# Super_Hub.net
KiCad netlist of a schematic drawn in EasyEDA Pro
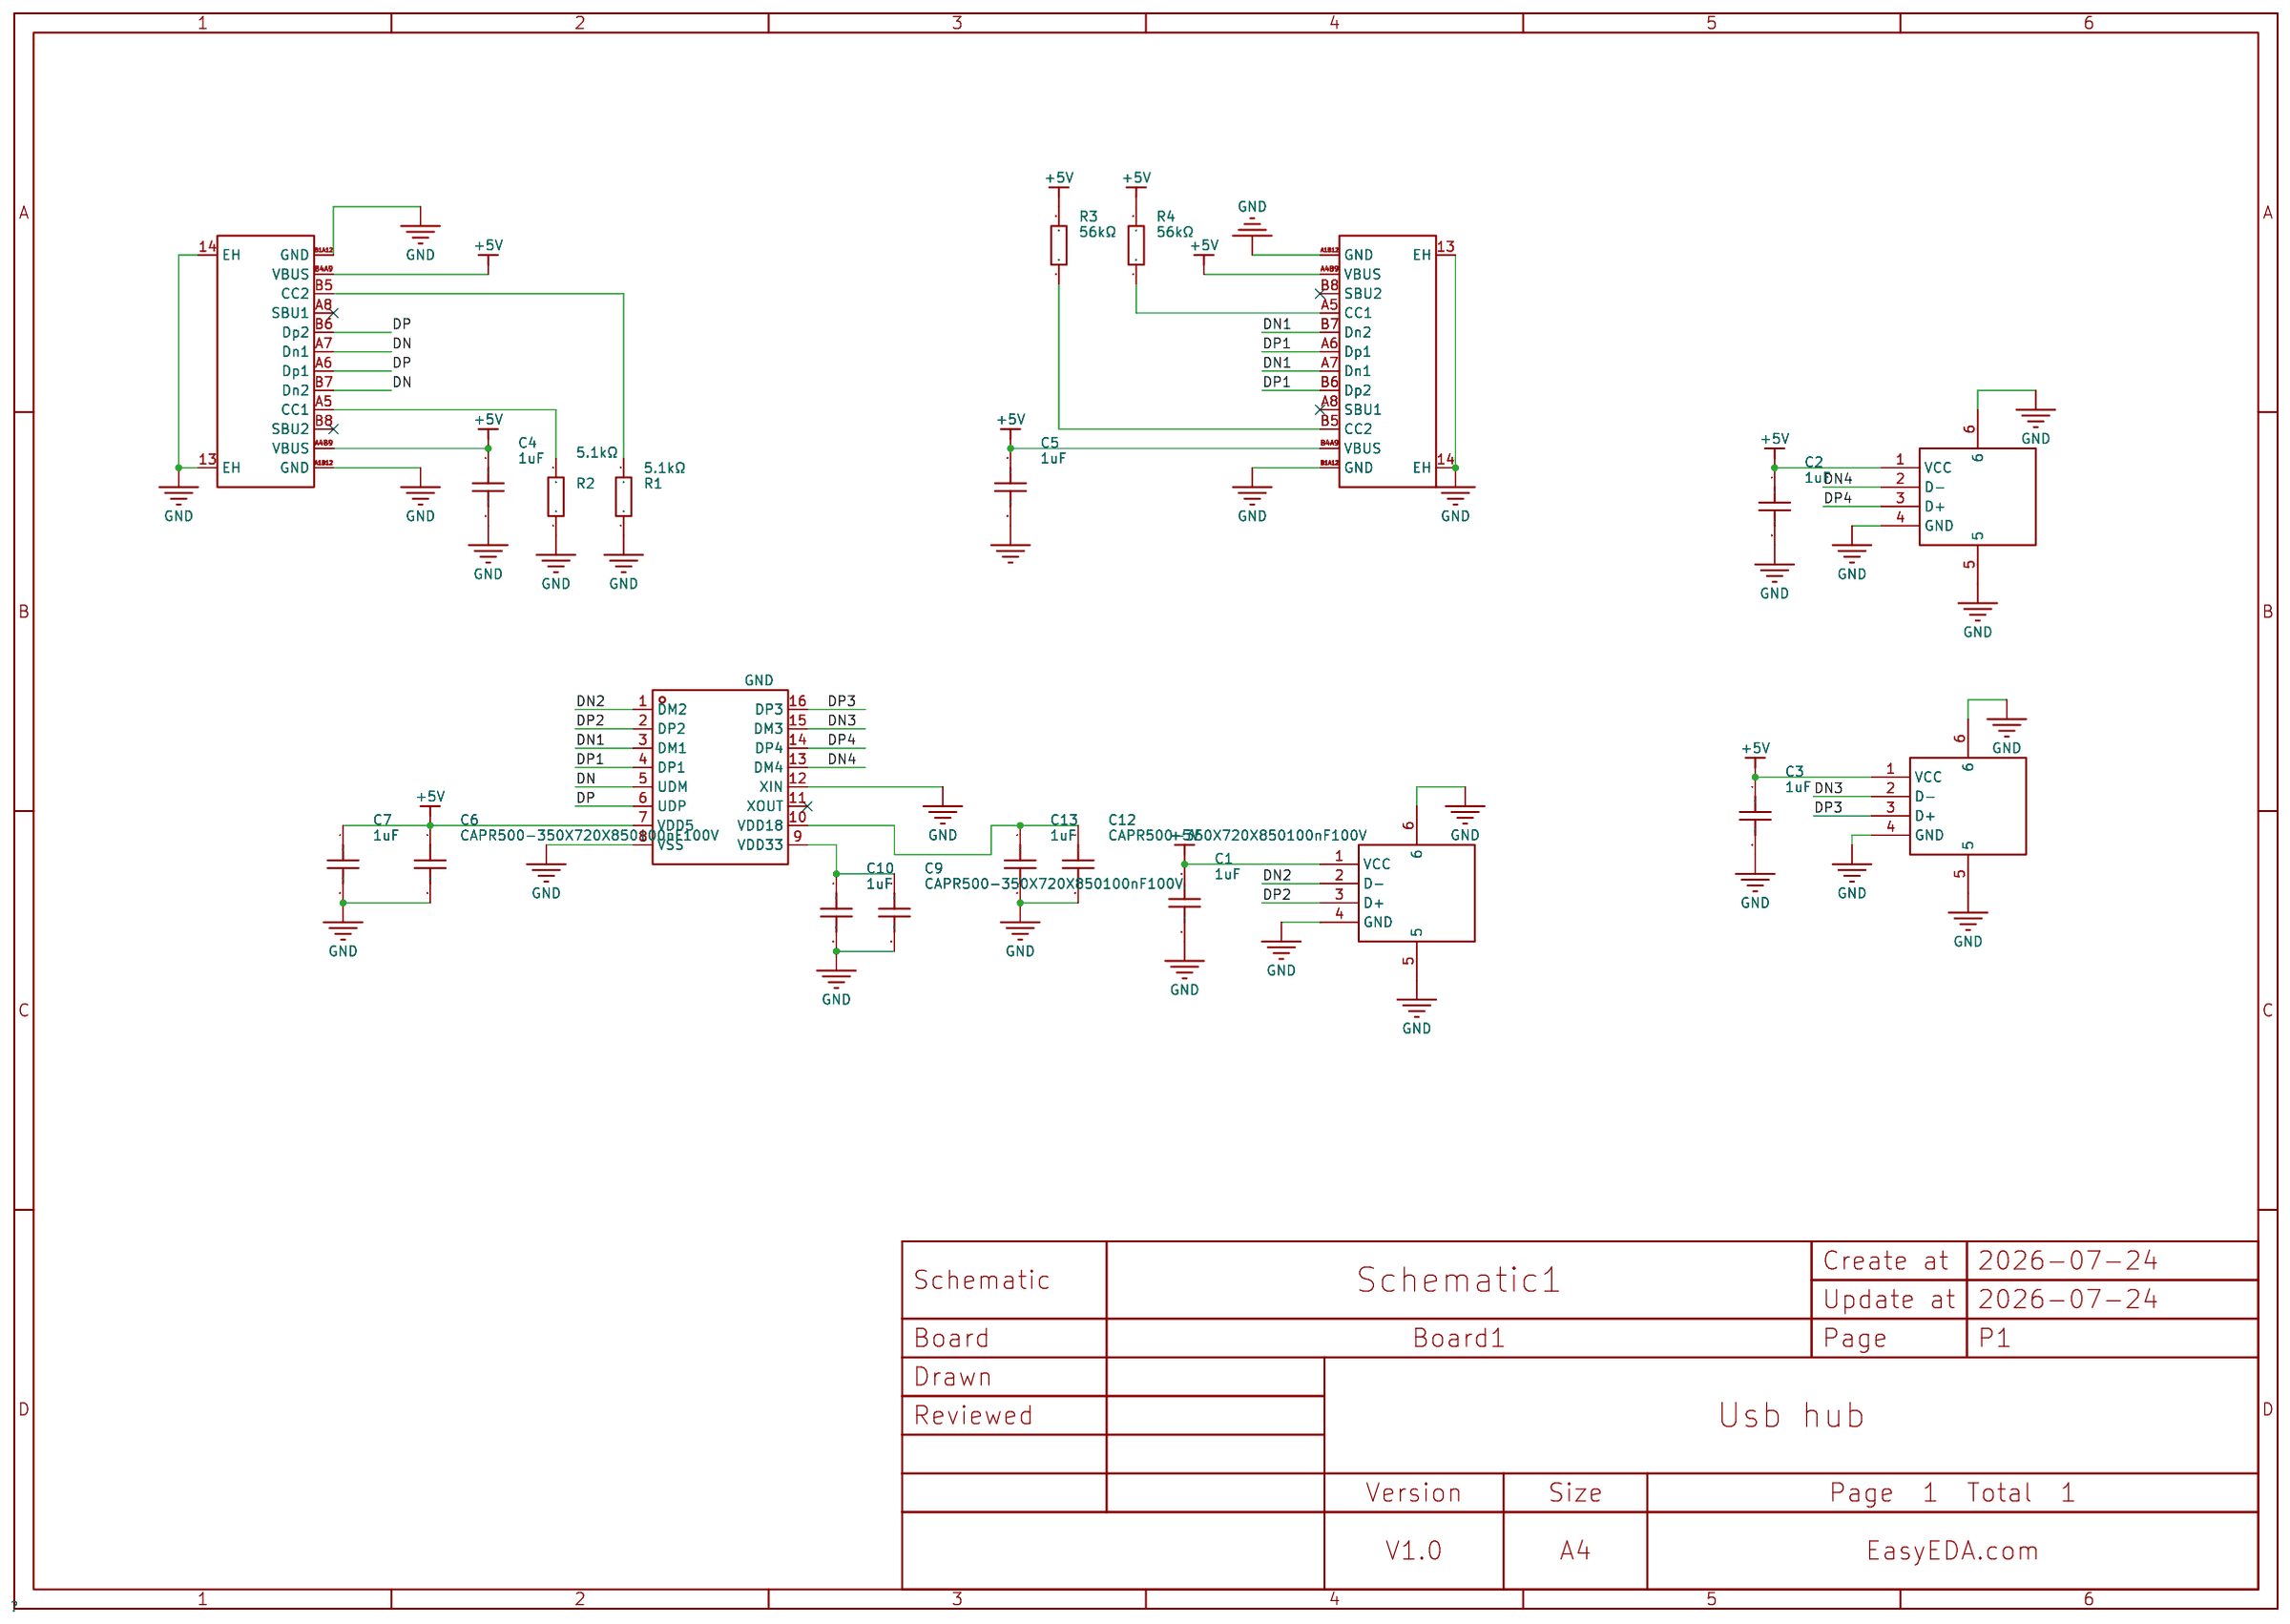
[diagram p0: schematic sheet]

(export (version "E")
  (design (tool "Eeschema 10.0.6"))
  (components
    (comp (ref "C1")
      (value "1uF")
      (footprint "easyedapro:C0603")
      (description "Capacitance:1uF Tolerance:±10% Tolerance:±10% Voltage Rating:50V Temperature Coefficient:X5R")
      (fields
        (field (name "Manufacturer Part") "CL10A105KB8NNNC")
        (field (name "Manufacturer") "SAMSUNG(三星)")
      )
      (libsource (lib "easyedapro") (part "CAP_OLD"))
    )
    (comp (ref "C2")
      (value "1uF")
      (footprint "easyedapro:C0603")
      (description "Capacitance:1uF Tolerance:±10% Tolerance:±10% Voltage Rating:50V Temperature Coefficient:X5R")
      (fields
        (field (name "Manufacturer Part") "CL10A105KB8NNNC")
        (field (name "Manufacturer") "SAMSUNG(三星)")
      )
      (libsource (lib "easyedapro") (part "CAP_OLD"))
    )
    (comp (ref "C3")
      (value "1uF")
      (footprint "easyedapro:C0603")
      (description "Capacitance:1uF Tolerance:±10% Tolerance:±10% Voltage Rating:50V Temperature Coefficient:X5R")
      (fields
        (field (name "Manufacturer Part") "CL10A105KB8NNNC")
        (field (name "Manufacturer") "SAMSUNG(三星)")
      )
      (libsource (lib "easyedapro") (part "CAP_OLD"))
    )
    (comp (ref "C4")
      (value "1uF")
      (footprint "easyedapro:C0603")
      (description "Capacitance:1uF Tolerance:±10% Tolerance:±10% Voltage Rating:50V Temperature Coefficient:X5R")
      (fields
        (field (name "Manufacturer Part") "CL10A105KB8NNNC")
        (field (name "Manufacturer") "SAMSUNG(三星)")
      )
      (libsource (lib "easyedapro") (part "CAP_OLD"))
    )
    (comp (ref "C5")
      (value "1uF")
      (footprint "easyedapro:C0603")
      (description "Capacitance:1uF Tolerance:±10% Tolerance:±10% Voltage Rating:50V Temperature Coefficient:X5R")
      (fields
        (field (name "Manufacturer Part") "CL10A105KB8NNNC")
        (field (name "Manufacturer") "SAMSUNG(三星)")
      )
      (libsource (lib "easyedapro") (part "CAP_OLD"))
    )
    (comp (ref "C6")
      (value "CAPR500-350X720X850100nF100V")
      (footprint "easyedapro:C0603")
      (libsource (lib "easyedapro") (part "CAP_OLD"))
    )
    (comp (ref "C7")
      (value "1uF")
      (footprint "easyedapro:C0603")
      (description "Capacitance:1uF Tolerance:±10% Tolerance:±10% Voltage Rating:50V Temperature Coefficient:X5R")
      (fields
        (field (name "Manufacturer Part") "CL10A105KB8NNNC")
        (field (name "Manufacturer") "SAMSUNG(三星)")
      )
      (libsource (lib "easyedapro") (part "CAP_OLD"))
    )
    (comp (ref "C9")
      (value "CAPR500-350X720X850100nF100V")
      (footprint "easyedapro:C0603")
      (libsource (lib "easyedapro") (part "CAP_OLD"))
    )
    (comp (ref "C10")
      (value "1uF")
      (footprint "easyedapro:C0603")
      (description "Capacitance:1uF Tolerance:±10% Tolerance:±10% Voltage Rating:50V Temperature Coefficient:X5R")
      (fields
        (field (name "Manufacturer Part") "CL10A105KB8NNNC")
        (field (name "Manufacturer") "SAMSUNG(三星)")
      )
      (libsource (lib "easyedapro") (part "CAP_OLD"))
    )
    (comp (ref "C12")
      (value "CAPR500-350X720X850100nF100V")
      (footprint "easyedapro:C0603")
      (libsource (lib "easyedapro") (part "CAP_OLD"))
    )
    (comp (ref "C13")
      (value "1uF")
      (footprint "easyedapro:C0603")
      (description "Capacitance:1uF Tolerance:±10% Tolerance:±10% Voltage Rating:50V Temperature Coefficient:X5R")
      (fields
        (field (name "Manufacturer Part") "CL10A105KB8NNNC")
        (field (name "Manufacturer") "SAMSUNG(三星)")
      )
      (libsource (lib "easyedapro") (part "CAP_OLD"))
    )
    (comp (ref "R1")
      (value "5.1kΩ")
      (footprint "easyedapro:R0603")
      (fields
        (field (name "Manufacturer Part") "0603WAF5101T5E")
        (field (name "Manufacturer") "UNI-ROYAL(厚声)")
        (field (name "Tolerance") "±1%")
      )
      (libsource (lib "easyedapro") (part "Res"))
    )
    (comp (ref "R2")
      (value "5.1kΩ")
      (footprint "easyedapro:R0603")
      (fields
        (field (name "Manufacturer Part") "0603WAF5101T5E")
        (field (name "Manufacturer") "UNI-ROYAL(厚声)")
        (field (name "Tolerance") "±1%")
      )
      (libsource (lib "easyedapro") (part "Res"))
    )
    (comp (ref "R3")
      (value "56kΩ")
      (footprint "easyedapro:R0603")
      (fields
        (field (name "Manufacturer Part") "0603WAF5602T5E")
        (field (name "Manufacturer") "UNI-ROYAL(厚声)")
        (field (name "Tolerance") "±1%")
      )
      (libsource (lib "easyedapro") (part "Res"))
    )
    (comp (ref "R4")
      (value "56kΩ")
      (footprint "easyedapro:R0603")
      (fields
        (field (name "Manufacturer Part") "0603WAF5602T5E")
        (field (name "Manufacturer") "UNI-ROYAL(厚声)")
        (field (name "Tolerance") "±1%")
      )
      (libsource (lib "easyedapro") (part "Res"))
    )
    (comp (ref "U1")
      (value "SL2.1s")
      (footprint "easyedapro:SSOP-16_L4.6-W2.6-P0.53-LS4.0-BL")
      (fields (field (name "Manufacturer") "CoreChips(和芯润德)"))
      (libsource (lib "easyedapro") (part "SL2.1S"))
    )
    (comp (ref "USB1")
      (value "10.0 QHHTZB6.3")
      (footprint "easyedapro:USB-A-TH_10.0QHHTZB6.3")
      (fields (field (name "Manufacturer") "SHOU HAN(首韩)"))
      (libsource (lib "easyedapro") (part "10.0 QHHTZB6.3"))
    )
    (comp (ref "USB2")
      (value "10.0 QHHTZB6.3")
      (footprint "easyedapro:USB-A-TH_10.0QHHTZB6.3")
      (fields (field (name "Manufacturer") "SHOU HAN(首韩)"))
      (libsource (lib "easyedapro") (part "10.0 QHHTZB6.3"))
    )
    (comp (ref "USB3")
      (value "10.0 QHHTZB6.3")
      (footprint "easyedapro:USB-A-TH_10.0QHHTZB6.3")
      (fields (field (name "Manufacturer") "SHOU HAN(首韩)"))
      (libsource (lib "easyedapro") (part "10.0 QHHTZB6.3"))
    )
    (comp (ref "USB4")
      (value "TYPE-C 16PIN 2MD(073)")
      (footprint "easyedapro:USB-C-SMD_TYPE-C-16PIN-2MD-073")
      (fields (field (name "Manufacturer") "SHOU HAN(首韩)"))
      (libsource (lib "easyedapro") (part "TYPE-C 16PIN 2MD(073)"))
    )
    (comp (ref "USB5")
      (value "TYPE-C 16PIN 2MD(073)")
      (footprint "easyedapro:USB-C-SMD_TYPE-C-16PIN-2MD-073")
      (fields (field (name "Manufacturer") "SHOU HAN(首韩)"))
      (libsource (lib "easyedapro") (part "TYPE-C 16PIN 2MD(073)"))
    )
  )
  (nets
    (net (code "1") (name "+5V") (class "Default")
      (node (ref "C1") (pin "1") (pinfunction "1_1") (pintype "input"))
      (node (ref "C2") (pin "1") (pinfunction "1_1") (pintype "input"))
      (node (ref "C3") (pin "1") (pinfunction "1_1") (pintype "input"))
      (node (ref "C4") (pin "1") (pinfunction "1_1") (pintype "input"))
      (node (ref "C5") (pin "1") (pinfunction "1_1") (pintype "input"))
      (node (ref "C6") (pin "1") (pinfunction "1_1") (pintype "input"))
      (node (ref "C7") (pin "1") (pinfunction "1_1") (pintype "input"))
      (node (ref "R3") (pin "2") (pinfunction "2_2") (pintype "input"))
      (node (ref "R4") (pin "2") (pinfunction "2_2") (pintype "input"))
      (node (ref "U1") (pin "7") (pinfunction "VDD5_7") (pintype "unspecified"))
      (node (ref "USB1") (pin "1") (pinfunction "VCC_1") (pintype "unspecified"))
      (node (ref "USB2") (pin "1") (pinfunction "VCC_1") (pintype "unspecified"))
      (node (ref "USB3") (pin "1") (pinfunction "VCC_1") (pintype "unspecified"))
      (node (ref "USB4") (pin "A4B9") (pinfunction "VBUS_A4B9") (pintype "unspecified"))
      (node (ref "USB4") (pin "B4A9") (pinfunction "VBUS_B4A9") (pintype "unspecified"))
      (node (ref "USB5") (pin "A4B9") (pinfunction "VBUS_A4B9") (pintype "unspecified"))
      (node (ref "USB5") (pin "B4A9") (pinfunction "VBUS_B4A9") (pintype "unspecified"))
    )
    (net (code "2") (name "/DN") (class "Default")
      (node (ref "U1") (pin "5") (pinfunction "UDM_5") (pintype "unspecified"))
      (node (ref "USB5") (pin "A7") (pinfunction "Dn1_A7") (pintype "unspecified"))
      (node (ref "USB5") (pin "B7") (pinfunction "Dn2_B7") (pintype "unspecified"))
    )
    (net (code "3") (name "/DN1") (class "Default")
      (node (ref "U1") (pin "3") (pinfunction "DM1_3") (pintype "unspecified"))
      (node (ref "USB4") (pin "A7") (pinfunction "Dn1_A7") (pintype "unspecified"))
      (node (ref "USB4") (pin "B7") (pinfunction "Dn2_B7") (pintype "unspecified"))
    )
    (net (code "4") (name "/DN2") (class "Default")
      (node (ref "U1") (pin "1") (pinfunction "DM2_1") (pintype "unspecified"))
      (node (ref "USB3") (pin "2") (pinfunction "D-_2") (pintype "unspecified"))
    )
    (net (code "5") (name "/DN3") (class "Default")
      (node (ref "U1") (pin "15") (pinfunction "DM3_15") (pintype "unspecified"))
      (node (ref "USB2") (pin "2") (pinfunction "D-_2") (pintype "unspecified"))
    )
    (net (code "6") (name "/DN4") (class "Default")
      (node (ref "U1") (pin "13") (pinfunction "DM4_13") (pintype "unspecified"))
      (node (ref "USB1") (pin "2") (pinfunction "D-_2") (pintype "unspecified"))
    )
    (net (code "7") (name "/DP") (class "Default")
      (node (ref "U1") (pin "6") (pinfunction "UDP_6") (pintype "unspecified"))
      (node (ref "USB5") (pin "A6") (pinfunction "Dp1_A6") (pintype "unspecified"))
      (node (ref "USB5") (pin "B6") (pinfunction "Dp2_B6") (pintype "unspecified"))
    )
    (net (code "8") (name "/DP1") (class "Default")
      (node (ref "U1") (pin "4") (pinfunction "DP1_4") (pintype "unspecified"))
      (node (ref "USB4") (pin "A6") (pinfunction "Dp1_A6") (pintype "unspecified"))
      (node (ref "USB4") (pin "B6") (pinfunction "Dp2_B6") (pintype "unspecified"))
    )
    (net (code "9") (name "/DP2") (class "Default")
      (node (ref "U1") (pin "2") (pinfunction "DP2_2") (pintype "unspecified"))
      (node (ref "USB3") (pin "3") (pinfunction "D+_3") (pintype "unspecified"))
    )
    (net (code "10") (name "/DP3") (class "Default")
      (node (ref "U1") (pin "16") (pinfunction "DP3_16") (pintype "unspecified"))
      (node (ref "USB2") (pin "3") (pinfunction "D+_3") (pintype "unspecified"))
    )
    (net (code "11") (name "/DP4") (class "Default")
      (node (ref "U1") (pin "14") (pinfunction "DP4_14") (pintype "unspecified"))
      (node (ref "USB1") (pin "3") (pinfunction "D+_3") (pintype "unspecified"))
    )
    (net (code "12") (name "GND") (class "Default")
      (node (ref "C1") (pin "2") (pinfunction "2_2") (pintype "input"))
      (node (ref "C10") (pin "2") (pinfunction "2_2") (pintype "input"))
      (node (ref "C12") (pin "2") (pinfunction "2_2") (pintype "input"))
      (node (ref "C13") (pin "2") (pinfunction "2_2") (pintype "input"))
      (node (ref "C2") (pin "2") (pinfunction "2_2") (pintype "input"))
      (node (ref "C3") (pin "2") (pinfunction "2_2") (pintype "input"))
      (node (ref "C4") (pin "2") (pinfunction "2_2") (pintype "input"))
      (node (ref "C5") (pin "2") (pinfunction "2_2") (pintype "input"))
      (node (ref "C6") (pin "2") (pinfunction "2_2") (pintype "input"))
      (node (ref "C7") (pin "2") (pinfunction "2_2") (pintype "input"))
      (node (ref "C9") (pin "2") (pinfunction "2_2") (pintype "input"))
      (node (ref "R1") (pin "1") (pinfunction "1_1") (pintype "input"))
      (node (ref "R2") (pin "1") (pinfunction "1_1") (pintype "input"))
      (node (ref "U1") (pin "12") (pinfunction "XIN_12") (pintype "unspecified"))
      (node (ref "U1") (pin "8") (pinfunction "VSS_8") (pintype "unspecified"))
      (node (ref "USB1") (pin "4") (pinfunction "GND_4") (pintype "unspecified"))
      (node (ref "USB1") (pin "5") (pinfunction "5_5") (pintype "unspecified"))
      (node (ref "USB1") (pin "6") (pinfunction "6_6") (pintype "unspecified"))
      (node (ref "USB2") (pin "4") (pinfunction "GND_4") (pintype "unspecified"))
      (node (ref "USB2") (pin "5") (pinfunction "5_5") (pintype "unspecified"))
      (node (ref "USB2") (pin "6") (pinfunction "6_6") (pintype "unspecified"))
      (node (ref "USB3") (pin "4") (pinfunction "GND_4") (pintype "unspecified"))
      (node (ref "USB3") (pin "5") (pinfunction "5_5") (pintype "unspecified"))
      (node (ref "USB3") (pin "6") (pinfunction "6_6") (pintype "unspecified"))
      (node (ref "USB4") (pin "13") (pinfunction "EH_13") (pintype "unspecified"))
      (node (ref "USB4") (pin "14") (pinfunction "EH_14") (pintype "unspecified"))
      (node (ref "USB4") (pin "A1B12") (pinfunction "GND_A1B12") (pintype "unspecified"))
      (node (ref "USB4") (pin "B1A12") (pinfunction "GND_B1A12") (pintype "unspecified"))
      (node (ref "USB5") (pin "13") (pinfunction "EH_13") (pintype "unspecified"))
      (node (ref "USB5") (pin "14") (pinfunction "EH_14") (pintype "unspecified"))
      (node (ref "USB5") (pin "A1B12") (pinfunction "GND_A1B12") (pintype "unspecified"))
      (node (ref "USB5") (pin "B1A12") (pinfunction "GND_B1A12") (pintype "unspecified"))
    )
    (net (code "13") (name "Net-(U1-VDD18)") (class "Default")
      (node (ref "C12") (pin "1") (pinfunction "1_1") (pintype "input"))
      (node (ref "C13") (pin "1") (pinfunction "1_1") (pintype "input"))
      (node (ref "U1") (pin "10") (pinfunction "VDD18_10") (pintype "unspecified"))
    )
    (net (code "14") (name "Net-(U1-VDD33)") (class "Default")
      (node (ref "C10") (pin "1") (pinfunction "1_1") (pintype "input"))
      (node (ref "C9") (pin "1") (pinfunction "1_1") (pintype "input"))
      (node (ref "U1") (pin "9") (pinfunction "VDD33_9") (pintype "unspecified"))
    )
    (net (code "15") (name "Net-(USB4-CC1)") (class "Default")
      (node (ref "R4") (pin "1") (pinfunction "1_1") (pintype "input"))
      (node (ref "USB4") (pin "A5") (pinfunction "CC1_A5") (pintype "unspecified"))
    )
    (net (code "16") (name "Net-(USB4-CC2)") (class "Default")
      (node (ref "R3") (pin "1") (pinfunction "1_1") (pintype "input"))
      (node (ref "USB4") (pin "B5") (pinfunction "CC2_B5") (pintype "unspecified"))
    )
    (net (code "17") (name "Net-(USB5-CC1)") (class "Default")
      (node (ref "R2") (pin "2") (pinfunction "2_2") (pintype "input"))
      (node (ref "USB5") (pin "A5") (pinfunction "CC1_A5") (pintype "unspecified"))
    )
    (net (code "18") (name "Net-(USB5-CC2)") (class "Default")
      (node (ref "R1") (pin "2") (pinfunction "2_2") (pintype "input"))
      (node (ref "USB5") (pin "B5") (pinfunction "CC2_B5") (pintype "unspecified"))
    )
    (net (code "19") (name "unconnected-(U1-XOUT-Pad11)") (class "Default")
      (node (ref "U1") (pin "11") (pinfunction "XOUT_11") (pintype "unspecified+no_connect"))
    )
    (net (code "20") (name "unconnected-(USB4-SBU1-PadA8)") (class "Default")
      (node (ref "USB4") (pin "A8") (pinfunction "SBU1_A8") (pintype "unspecified+no_connect"))
    )
    (net (code "21") (name "unconnected-(USB4-SBU2-PadB8)") (class "Default")
      (node (ref "USB4") (pin "B8") (pinfunction "SBU2_B8") (pintype "unspecified+no_connect"))
    )
    (net (code "22") (name "unconnected-(USB5-SBU1-PadA8)") (class "Default")
      (node (ref "USB5") (pin "A8") (pinfunction "SBU1_A8") (pintype "unspecified+no_connect"))
    )
    (net (code "23") (name "unconnected-(USB5-SBU2-PadB8)") (class "Default")
      (node (ref "USB5") (pin "B8") (pinfunction "SBU2_B8") (pintype "unspecified+no_connect"))
    )
  )
)
